# Sonar-Amplifier.net
KiCad netlist of a schematic drawn in EAGLE
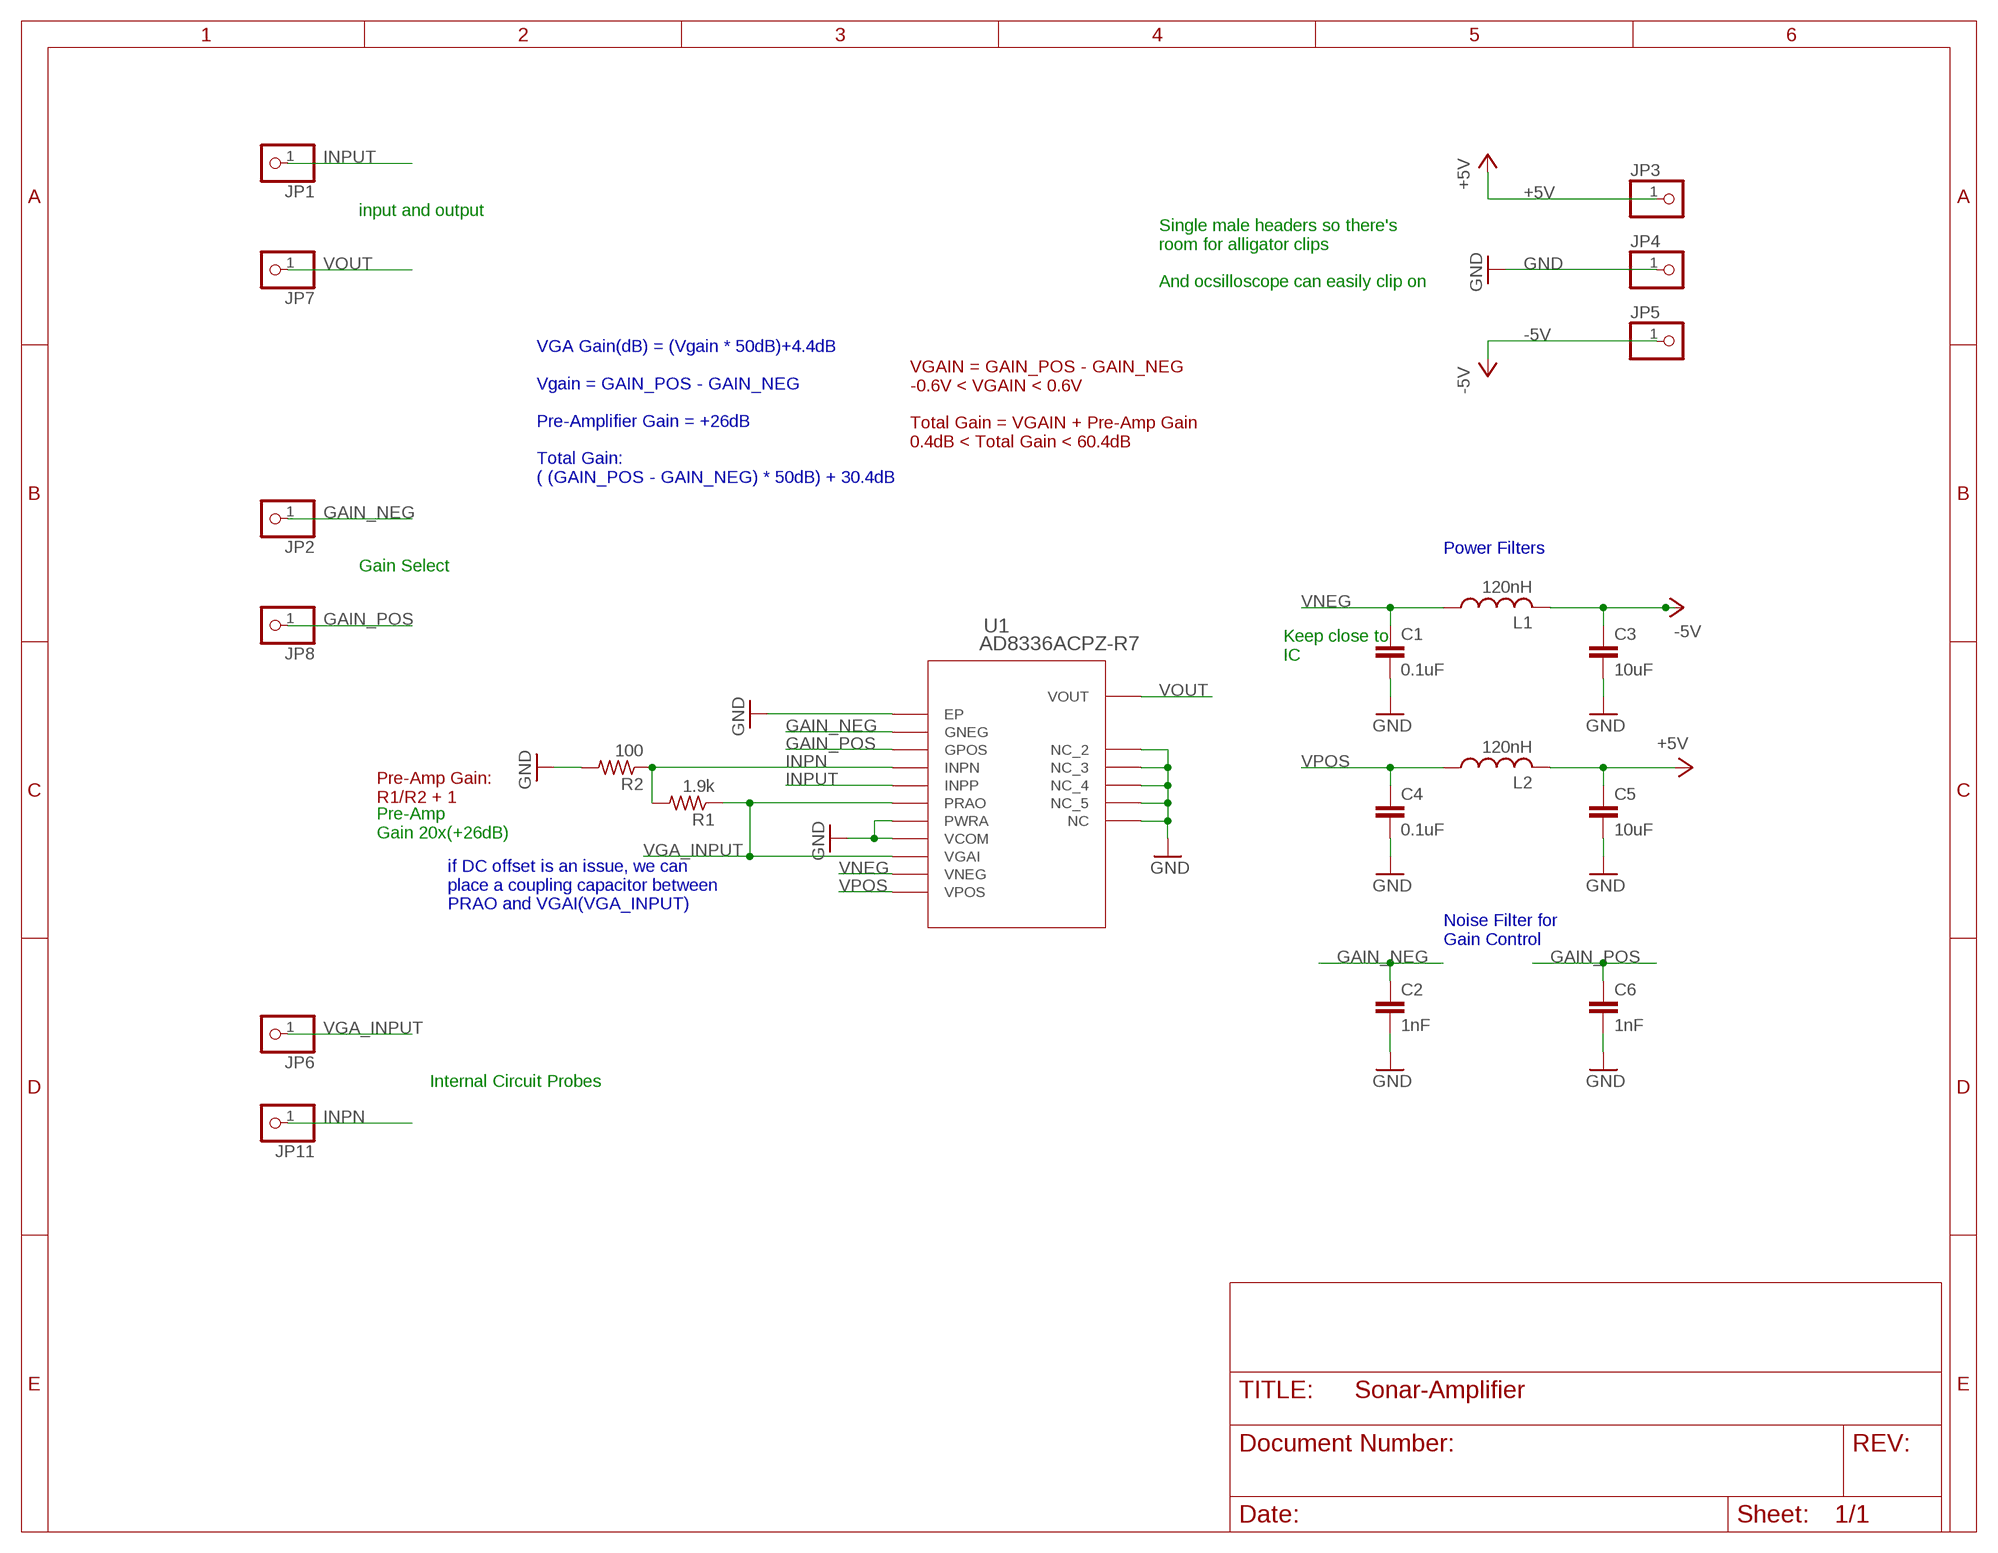
[diagram p0: schematic, sheet 1]

(export (version "E")
  (design (tool "Eeschema 10.0.6"))
  (components
    (comp (ref "C1")
      (value "0.1uF")
      (footprint "eagle-import:C0603")
      (libsource (lib "eagle-import") (part "C-EUC0603"))
    )
    (comp (ref "C2")
      (value "1nF")
      (footprint "eagle-import:C0603")
      (libsource (lib "eagle-import") (part "C-EUC0603"))
    )
    (comp (ref "C3")
      (value "10uF")
      (footprint "eagle-import:C1206")
      (libsource (lib "eagle-import") (part "resistor_348_C-EUC1206"))
    )
    (comp (ref "C4")
      (value "0.1uF")
      (footprint "eagle-import:C0603")
      (libsource (lib "eagle-import") (part "C-EUC0603"))
    )
    (comp (ref "C5")
      (value "10uF")
      (footprint "eagle-import:C1206")
      (libsource (lib "eagle-import") (part "resistor_348_C-EUC1206"))
    )
    (comp (ref "C6")
      (value "1nF")
      (footprint "eagle-import:C0603")
      (libsource (lib "eagle-import") (part "C-EUC0603"))
    )
    (comp (ref "JP1")
      (value "PINHD-1X1")
      (footprint "eagle-import:1X01")
      (libsource (lib "eagle-import") (part "PINHD-1X1"))
    )
    (comp (ref "JP2")
      (value "PINHD-1X1")
      (footprint "eagle-import:1X01")
      (libsource (lib "eagle-import") (part "PINHD-1X1"))
    )
    (comp (ref "JP3")
      (value "PINHD-1X1")
      (footprint "eagle-import:1X01")
      (libsource (lib "eagle-import") (part "PINHD-1X1"))
    )
    (comp (ref "JP4")
      (value "PINHD-1X1")
      (footprint "eagle-import:1X01")
      (libsource (lib "eagle-import") (part "PINHD-1X1"))
    )
    (comp (ref "JP5")
      (value "PINHD-1X1")
      (footprint "eagle-import:1X01")
      (libsource (lib "eagle-import") (part "PINHD-1X1"))
    )
    (comp (ref "JP6")
      (value "PINHD-1X1")
      (footprint "eagle-import:1X01")
      (libsource (lib "eagle-import") (part "PINHD-1X1"))
    )
    (comp (ref "JP7")
      (value "PINHD-1X1")
      (footprint "eagle-import:1X01")
      (libsource (lib "eagle-import") (part "PINHD-1X1"))
    )
    (comp (ref "JP8")
      (value "PINHD-1X1")
      (footprint "eagle-import:1X01")
      (libsource (lib "eagle-import") (part "PINHD-1X1"))
    )
    (comp (ref "JP11")
      (value "PINHD-1X1")
      (footprint "eagle-import:1X01")
      (libsource (lib "eagle-import") (part "PINHD-1X1"))
    )
    (comp (ref "L1")
      (value "120nH")
      (footprint "eagle-import:L3225P")
      (libsource (lib "eagle-import") (part "L-USL3225P"))
    )
    (comp (ref "L2")
      (value "120nH")
      (footprint "eagle-import:L3225P")
      (libsource (lib "eagle-import") (part "L-USL3225P"))
    )
    (comp (ref "R1")
      (value "1.9k")
      (footprint "eagle-import:R0603")
      (libsource (lib "eagle-import") (part "R-US_R0603"))
    )
    (comp (ref "R2")
      (value "100")
      (footprint "eagle-import:R0603")
      (libsource (lib "eagle-import") (part "R-US_R0603"))
    )
    (comp (ref "U1")
      (value "AD8336ACPZ-R7")
      (footprint "eagle-import:CP_16_4")
      (fields (field (name "MANUFACTURER_PART_NUMBER") "AD8336ACPZR7"))
      (libsource (lib "eagle-import") (part "AD8336ACPZ-R7"))
    )
  )
  (nets
    (net (code "1") (name "+5V") (class "Default")
      (node (ref "C5") (pin "1") (pinfunction "1_1") (pintype "passive"))
      (node (ref "JP3") (pin "1") (pinfunction "1_1") (pintype "passive"))
      (node (ref "L2") (pin "2") (pinfunction "2_2") (pintype "passive"))
    )
    (net (code "2") (name "-5V") (class "Default")
      (node (ref "C3") (pin "1") (pinfunction "1_1") (pintype "passive"))
      (node (ref "JP5") (pin "1") (pinfunction "1_1") (pintype "passive"))
      (node (ref "L1") (pin "2") (pinfunction "2_2") (pintype "passive"))
    )
    (net (code "3") (name "/GAIN_NEG") (class "Default")
      (node (ref "C2") (pin "1") (pinfunction "1_1") (pintype "passive"))
      (node (ref "JP2") (pin "1") (pinfunction "1_1") (pintype "passive"))
      (node (ref "U1") (pin "GNEG") (pinfunction "GNEG_GNEG") (pintype "passive"))
    )
    (net (code "4") (name "/GAIN_POS") (class "Default")
      (node (ref "C6") (pin "1") (pinfunction "1_1") (pintype "passive"))
      (node (ref "JP8") (pin "1") (pinfunction "1_1") (pintype "passive"))
      (node (ref "U1") (pin "GPOS") (pinfunction "GPOS_GPOS") (pintype "passive"))
    )
    (net (code "5") (name "/INPN") (class "Default")
      (node (ref "JP11") (pin "1") (pinfunction "1_1") (pintype "passive"))
      (node (ref "R1") (pin "2") (pinfunction "2_2") (pintype "passive"))
      (node (ref "R2") (pin "1") (pinfunction "1_1") (pintype "passive"))
      (node (ref "U1") (pin "INPN") (pinfunction "INPN_INPN") (pintype "passive"))
    )
    (net (code "6") (name "/INPUT") (class "Default")
      (node (ref "JP1") (pin "1") (pinfunction "1_1") (pintype "passive"))
      (node (ref "U1") (pin "INPP") (pinfunction "INPP_INPP") (pintype "passive"))
    )
    (net (code "7") (name "/VGA_INPUT") (class "Default")
      (node (ref "JP6") (pin "1") (pinfunction "1_1") (pintype "passive"))
      (node (ref "R1") (pin "1") (pinfunction "1_1") (pintype "passive"))
      (node (ref "U1") (pin "PRAO") (pinfunction "PRAO_PRAO") (pintype "passive"))
      (node (ref "U1") (pin "VGAI") (pinfunction "VGAI_VGAI") (pintype "passive"))
    )
    (net (code "8") (name "/VNEG") (class "Default")
      (node (ref "C1") (pin "1") (pinfunction "1_1") (pintype "passive"))
      (node (ref "L1") (pin "1") (pinfunction "1_1") (pintype "passive"))
      (node (ref "U1") (pin "VNEG") (pinfunction "VNEG_VNEG") (pintype "passive"))
    )
    (net (code "9") (name "/VOUT") (class "Default")
      (node (ref "JP7") (pin "1") (pinfunction "1_1") (pintype "passive"))
      (node (ref "U1") (pin "VOUT") (pinfunction "VOUT_VOUT") (pintype "passive"))
    )
    (net (code "10") (name "/VPOS") (class "Default")
      (node (ref "C4") (pin "1") (pinfunction "1_1") (pintype "passive"))
      (node (ref "L2") (pin "1") (pinfunction "1_1") (pintype "passive"))
      (node (ref "U1") (pin "VPOS") (pinfunction "VPOS_VPOS") (pintype "passive"))
    )
    (net (code "11") (name "GND") (class "Default")
      (node (ref "C1") (pin "2") (pinfunction "2_2") (pintype "passive"))
      (node (ref "C2") (pin "2") (pinfunction "2_2") (pintype "passive"))
      (node (ref "C3") (pin "2") (pinfunction "2_2") (pintype "passive"))
      (node (ref "C4") (pin "2") (pinfunction "2_2") (pintype "passive"))
      (node (ref "C5") (pin "2") (pinfunction "2_2") (pintype "passive"))
      (node (ref "C6") (pin "2") (pinfunction "2_2") (pintype "passive"))
      (node (ref "JP4") (pin "1") (pinfunction "1_1") (pintype "passive"))
      (node (ref "R2") (pin "2") (pinfunction "2_2") (pintype "passive"))
      (node (ref "U1") (pin "GND1") (pinfunction "EP_GND1") (pintype "passive"))
      (node (ref "U1") (pin "NC") (pinfunction "NC_NC") (pintype "passive"))
      (node (ref "U1") (pin "NC1") (pinfunction "NC_2_NC1") (pintype "passive"))
      (node (ref "U1") (pin "NC2") (pinfunction "NC_3_NC2") (pintype "passive"))
      (node (ref "U1") (pin "NC3") (pinfunction "NC_4_NC3") (pintype "passive"))
      (node (ref "U1") (pin "NC4") (pinfunction "NC_5_NC4") (pintype "passive"))
      (node (ref "U1") (pin "PWRA") (pinfunction "PWRA_PWRA") (pintype "passive"))
      (node (ref "U1") (pin "VCOM") (pinfunction "VCOM_VCOM") (pintype "passive"))
    )
  )
)
